# Input_channel.net
KiCad netlist of a schematic drawn in Altium Designer
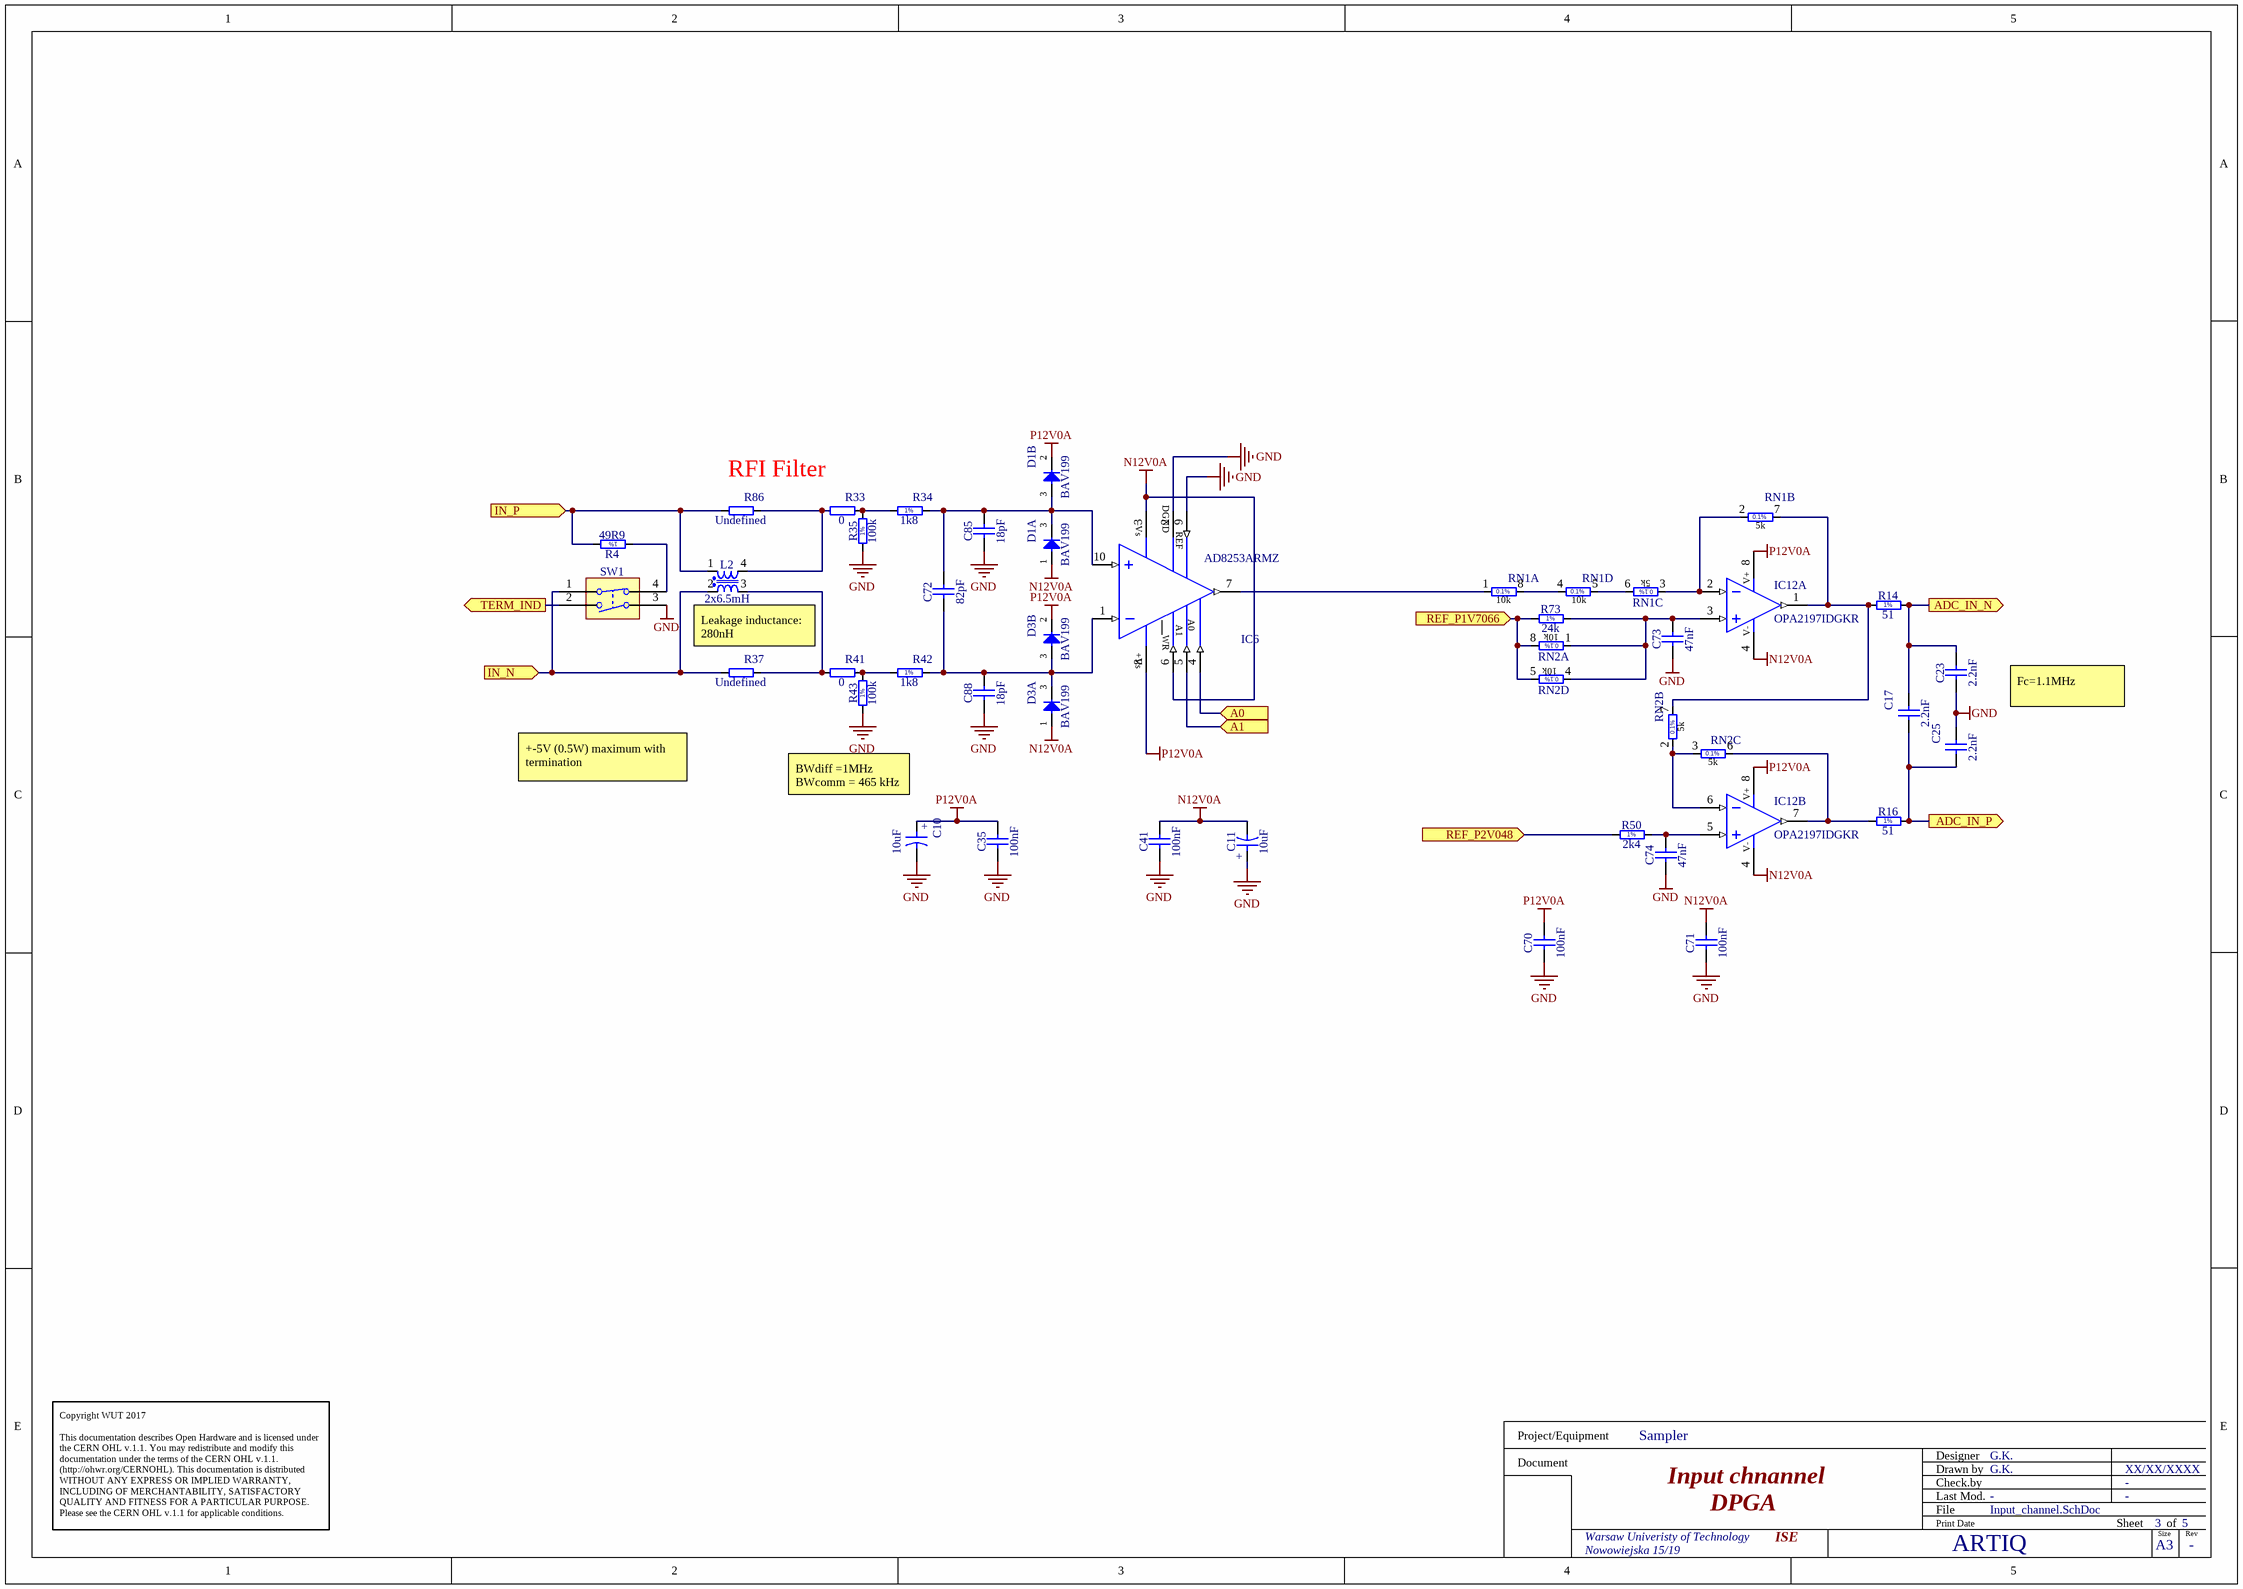
[diagram p0: Input_channel.SchDoc]

(export (version "E")
  (design (tool "Eeschema 10.0.6"))
  (components
    (comp (ref "C10")
      (value "10uF")
      (footprint "CAPMP3216X180N")
      (description "Polarised capacitor")
      (fields
        (field (name "PART NUMBER") "CTE3216-18_10UF_16V_20%_AVX_TCJ")
        (field (name "VOLTAGE") "16V")
        (field (name "AUTHOR") "CERN DEM JLC")
      )
      (libsource (lib "Capacitors") (part "Capacitor - polarized"))
    )
    (comp (ref "C11")
      (value "10uF")
      (footprint "CAPMP3216X180N")
      (description "Polarised capacitor")
      (fields
        (field (name "PART NUMBER") "CTE3216-18_10UF_16V_20%_AVX_TCJ")
        (field (name "VOLTAGE") "16V")
        (field (name "AUTHOR") "CERN DEM JLC")
      )
      (libsource (lib "Capacitors") (part "Capacitor - polarized"))
    )
    (comp (ref "C17")
      (value "2.2nF")
      (footprint "CAPC2013X100N")
      (description "Non-polarised capacitor")
      (fields
        (field (name "PART NUMBER") "CC0805_2.2NF_25V_1%_C0G")
        (field (name "VOLTAGE") "25V")
        (field (name "AUTHOR") "CERN DEM JLC")
      )
      (libsource (lib "Capacitors") (part "Capacitor - non polarized"))
    )
    (comp (ref "C23")
      (value "2.2nF")
      (footprint "CAPC2013X100N")
      (description "Non-polarised capacitor")
      (fields
        (field (name "PART NUMBER") "CC0805_2.2NF_25V_1%_C0G")
        (field (name "VOLTAGE") "25V")
        (field (name "AUTHOR") "CERN DEM JLC")
      )
      (libsource (lib "Capacitors") (part "Capacitor - non polarized"))
    )
    (comp (ref "C25")
      (value "2.2nF")
      (footprint "CAPC2013X100N")
      (description "Non-polarised capacitor")
      (fields
        (field (name "PART NUMBER") "CC0805_2.2NF_25V_1%_C0G")
        (field (name "VOLTAGE") "25V")
        (field (name "AUTHOR") "CERN DEM JLC")
      )
      (libsource (lib "Capacitors") (part "Capacitor - non polarized"))
    )
    (comp (ref "C35")
      (value "100nF")
      (footprint "CAPC1005X55N")
      (description "Non-polarised capacitor")
      (fields
        (field (name "PART NUMBER") "CC0402_100NF_16V_10%_X7R")
        (field (name "VOLTAGE") "16V")
        (field (name "AUTHOR") "CERN DEM JLC")
      )
      (libsource (lib "Capacitors") (part "Capacitor - non polarized"))
    )
    (comp (ref "C41")
      (value "100nF")
      (footprint "CAPC1005X55N")
      (description "Non-polarised capacitor")
      (fields
        (field (name "PART NUMBER") "CC0402_100NF_16V_10%_X7R")
        (field (name "VOLTAGE") "16V")
        (field (name "AUTHOR") "CERN DEM JLC")
      )
      (libsource (lib "Capacitors") (part "Capacitor - non polarized"))
    )
    (comp (ref "C70")
      (value "100nF")
      (footprint "CAPC1005X55N")
      (description "Non-polarised capacitor")
      (fields
        (field (name "PART NUMBER") "CC0402_100NF_16V_10%_X7R")
        (field (name "VOLTAGE") "16V")
        (field (name "AUTHOR") "CERN DEM JLC")
      )
      (libsource (lib "Capacitors") (part "Capacitor - non polarized"))
    )
    (comp (ref "C71")
      (value "100nF")
      (footprint "CAPC1005X55N")
      (description "Non-polarised capacitor")
      (fields
        (field (name "PART NUMBER") "CC0402_100NF_16V_10%_X7R")
        (field (name "VOLTAGE") "16V")
        (field (name "AUTHOR") "CERN DEM JLC")
      )
      (libsource (lib "Capacitors") (part "Capacitor - non polarized"))
    )
    (comp (ref "C72")
      (value "82pF")
      (footprint "CAPC2012X90N")
      (description "Non-polarised capacitor")
      (fields
        (field (name "PART NUMBER") "CC0805_82PF_100V_1%_NP0_AVX_08051A820FAT2A")
        (field (name "VOLTAGE") "100V")
        (field (name "AUTHOR") "CERN DEM WB")
      )
      (libsource (lib "Capacitors") (part "Capacitor - non polarized"))
    )
    (comp (ref "C73")
      (value "47nF")
      (footprint "CAPC2012X135N")
      (description "Non-polarised capacitor")
      (fields
        (field (name "PART NUMBER") "CC0805_47NF_25V_5%_C0G")
        (field (name "VOLTAGE") "25V")
        (field (name "AUTHOR") "CERN DEM JLC")
      )
      (libsource (lib "Capacitors") (part "Capacitor - non polarized"))
    )
    (comp (ref "C74")
      (value "47nF")
      (footprint "CAPC2012X135N")
      (description "Non-polarised capacitor")
      (fields
        (field (name "PART NUMBER") "CC0805_47NF_25V_5%_C0G")
        (field (name "VOLTAGE") "25V")
        (field (name "AUTHOR") "CERN DEM JLC")
      )
      (libsource (lib "Capacitors") (part "Capacitor - non polarized"))
    )
    (comp (ref "C85")
      (value "18pF")
      (footprint "CAPC1608X87N")
      (description "Non-polarised capacitor")
      (fields
        (field (name "PART NUMBER") "CC0603_18PF_50V_5%_NP0")
        (field (name "VOLTAGE") "50V")
        (field (name "AUTHOR") "CERN DEM JLC")
      )
      (libsource (lib "Capacitors") (part "Capacitor - non polarized"))
    )
    (comp (ref "C88")
      (value "18pF")
      (footprint "CAPC1608X87N")
      (description "Non-polarised capacitor")
      (fields
        (field (name "PART NUMBER") "CC0603_18PF_50V_5%_NP0")
        (field (name "VOLTAGE") "50V")
        (field (name "AUTHOR") "CERN DEM JLC")
      )
      (libsource (lib "Capacitors") (part "Capacitor - non polarized"))
    )
    (comp (ref "D1")
      (value "BAV199")
      (footprint "SOT95P240X110-3N")
      (description "Serial Diode")
      (fields
        (field (name "VOLTAGE") "75V")
        (field (name "POWER") "250mW")
        (field (name "AUTHOR") "CERN DEM JMW")
      )
      (libsource (lib "ICs And Semiconductors") (part "Diode x2 A1C3_A3C2"))
    )
    (comp (ref "D3")
      (value "BAV199")
      (footprint "SOT95P240X110-3N")
      (description "Serial Diode")
      (fields
        (field (name "VOLTAGE") "75V")
        (field (name "POWER") "250mW")
        (field (name "AUTHOR") "CERN DEM JMW")
      )
      (libsource (lib "ICs And Semiconductors") (part "Diode x2 A1C3_A3C2"))
    )
    (comp (ref "IC6")
      (value "AD8253ARMZ")
      (footprint "SOP50P490X110-10N")
      (description "10MHz, 20V/us, G= 1, 10, 100, 1000 iCMOS Programmable Gain Instrumentation Amplifier")
      (fields (field (name "MANUFACTURER") "ANALOG DEVICES") (field (name "AUTHOR") "CERN DEM JLC"))
      (libsource (lib "ICs And Semiconductors") (part "AD8253"))
    )
    (comp (ref "IC12")
      (value "OPA2197IDGKR")
      (footprint "SOP65P490X110-8N")
      (description "36-V, Precision, Rail-to-Rail Input Output, Low Offset Voltage Op Amp 8-VSSOP")
      (fields (field (name "MANUFACTURER") "TEXAS INSTRUMENTS") (field (name "AUTHOR") "GK"))
      (libsource (lib "LIBRARY_SCH") (part "OA_OPA2197IDGKR"))
    )
    (comp (ref "L2")
      (value "2x6.5mH")
      (footprint "IND_WURTH_WE-SL2")
      (description "Inductor Common Mode")
      (fields
        (field (name "PART NUMBER") "IND_6.5MH_50%_WURTH_WE-SL2-744229")
        (field (name "POWER") "400mA")
        (field (name "AUTHOR") "CERN DEM JLC")
      )
      (libsource (lib "Inductors & Transformers") (part "Inductor Common Mode 1Dot-4 2Dot-3"))
    )
    (comp (ref "R4")
      (value "49R9")
      (footprint "RESC6331X70N")
      (description "Resistor - 1%")
      (fields
        (field (name "PART NUMBER") "R2512_49R9_1%_1W_100PPM_VISHAY_CRCW")
        (field (name "POWER") "1W")
        (field (name "AUTHOR") "CERN DEM JLC")
      )
      (libsource (lib "Resistors") (part "Resistor - 1%"))
    )
    (comp (ref "R14")
      (value "51")
      (footprint "RESC1005X40N")
      (description "Resistor - 1%")
      (fields
        (field (name "PART NUMBER") "R0402_51R_1%_0.0625W_100PPM")
        (field (name "POWER") "0.0625W")
        (field (name "AUTHOR") "CERN DEM JLC")
      )
      (libsource (lib "Resistors") (part "Resistor - 1%"))
    )
    (comp (ref "R16")
      (value "51")
      (footprint "RESC1005X40N")
      (description "Resistor - 1%")
      (fields
        (field (name "PART NUMBER") "R0402_51R_1%_0.0625W_100PPM")
        (field (name "POWER") "0.0625W")
        (field (name "AUTHOR") "CERN DEM JLC")
      )
      (libsource (lib "Resistors") (part "Resistor - 1%"))
    )
    (comp (ref "R33")
      (value "0")
      (footprint "RESC1608X55N")
      (description "Resistor")
      (fields
        (field (name "PART NUMBER") "R0603_0R_JUMPER")
        (field (name "MANUFACTURER") "GENERIC")
        (field (name "AUTHOR") "CERN DEM JLC")
      )
      (libsource (lib "Resistors") (part "Resistor"))
    )
    (comp (ref "R34")
      (value "1k8")
      (footprint "RESC1608X55N")
      (description "Resistor - 1%")
      (fields
        (field (name "PART NUMBER") "R0603_1K8_1%_0.1W_100PPM")
        (field (name "POWER") "0.1W")
        (field (name "AUTHOR") "CERN DEM JLC")
      )
      (libsource (lib "Resistors") (part "Resistor - 1%"))
    )
    (comp (ref "R35")
      (value "100k")
      (footprint "RESC1608X55N")
      (description "Resistor - 1%")
      (fields
        (field (name "PART NUMBER") "R0603_100K_1%_0.1W_100PPM")
        (field (name "POWER") "0.1W")
        (field (name "AUTHOR") "CERN DEM JLC")
      )
      (libsource (lib "Resistors") (part "Resistor - 1%"))
    )
    (comp (ref "R37")
      (value "Undefined")
      (footprint "RESC1608X55N")
      (description "Resistor")
      (fields (field (name "PART NUMBER") "R0603_NO-VALUE") (field (name "AUTHOR") "CERN DEM JLC"))
      (libsource (lib "Resistors") (part "Resistor"))
    )
    (comp (ref "R41")
      (value "0")
      (footprint "RESC1608X55N")
      (description "Resistor")
      (fields
        (field (name "PART NUMBER") "R0603_0R_JUMPER")
        (field (name "MANUFACTURER") "GENERIC")
        (field (name "AUTHOR") "CERN DEM JLC")
      )
      (libsource (lib "Resistors") (part "Resistor"))
    )
    (comp (ref "R42")
      (value "1k8")
      (footprint "RESC1608X55N")
      (description "Resistor - 1%")
      (fields
        (field (name "PART NUMBER") "R0603_1K8_1%_0.1W_100PPM")
        (field (name "POWER") "0.1W")
        (field (name "AUTHOR") "CERN DEM JLC")
      )
      (libsource (lib "Resistors") (part "Resistor - 1%"))
    )
    (comp (ref "R43")
      (value "100k")
      (footprint "RESC1608X55N")
      (description "Resistor - 1%")
      (fields
        (field (name "PART NUMBER") "R0603_100K_1%_0.1W_100PPM")
        (field (name "POWER") "0.1W")
        (field (name "AUTHOR") "CERN DEM JLC")
      )
      (libsource (lib "Resistors") (part "Resistor - 1%"))
    )
    (comp (ref "R50")
      (value "2k4")
      (footprint "RESC1005X40N")
      (description "Resistor - 1%")
      (fields
        (field (name "PART NUMBER") "R0402_2K4_1%_0.0625W_100PPM")
        (field (name "POWER") "0.0625W")
        (field (name "AUTHOR") "CERN DEM JLC")
      )
      (libsource (lib "Resistors") (part "Resistor - 1%"))
    )
    (comp (ref "R73")
      (value "24k")
      (footprint "RESC1608X55N")
      (description "Resistor - 1%")
      (fields
        (field (name "PART NUMBER") "R0603_24K_1%_0.1W_100PPM")
        (field (name "POWER") "0.1W")
        (field (name "AUTHOR") "CERN DEM JLC")
      )
      (libsource (lib "Resistors") (part "Resistor - 1%"))
    )
    (comp (ref "R86")
      (value "Undefined")
      (footprint "RESC1608X55N")
      (description "Resistor")
      (fields (field (name "PART NUMBER") "R0603_NO-VALUE") (field (name "AUTHOR") "CERN DEM JLC"))
      (libsource (lib "Resistors") (part "Resistor"))
    )
    (comp (ref "RN1")
      (value "10k 5K 5K 10K")
      (footprint "SOIC127P600X175-8N")
      (description "DIL8 Resistor Network 4 Resistors 10k-5k-5k-10k 0.1%")
      (fields
        (field (name "PART NUMBER") "RN_10K_5K_VISHAY_AORN2-1AT3")
        (field (name "POWER") "4x0.1W")
        (field (name "AUTHOR") "CERN DEM JLC")
      )
      (libsource (lib "Resistors") (part "RN DIL8_4xR_10k-5k-5k-10k_0.1%"))
    )
    (comp (ref "RN2")
      (value "10k 5K 5K 10K")
      (footprint "SOIC127P600X175-8N")
      (description "DIL8 Resistor Network 4 Resistors 10k-5k-5k-10k 0.1%")
      (fields
        (field (name "PART NUMBER") "RN_10K_5K_VISHAY_AORN2-1AT3")
        (field (name "POWER") "4x0.1W")
        (field (name "AUTHOR") "CERN DEM JLC")
      )
      (libsource (lib "Resistors") (part "RN DIL8_4xR_10k-5k-5k-10k_0.1%"))
    )
    (comp (ref "SW1")
      (value "Switch")
      (footprint "SW_CTS_204-121ST")
      (description "2x SPST DIP Switch 1NO + 1NF")
      (fields
        (field (name "PART NUMBER") "SW_CTS_204-121ST")
        (field (name "MANUFACTURER") "CTS")
        (field (name "AUTHOR") "CERN DEM JLC")
      )
      (libsource (lib "Eletro-mechanical") (part "SW_CTS_204-121ST"))
    )
  )
  (nets
    (net (code "1") (name "/A0") (class "Default")
      (node (ref "IC6") (pin "4") (pinfunction "A0_4") (pintype "input"))
    )
    (net (code "2") (name "/A1") (class "Default")
      (node (ref "IC6") (pin "5") (pinfunction "A1_5") (pintype "input"))
    )
    (net (code "3") (name "/ADC_IN_N") (class "Default")
      (node (ref "C17") (pin "2") (pinfunction "2_2") (pintype "passive"))
      (node (ref "C23") (pin "2") (pinfunction "2_2") (pintype "passive"))
      (node (ref "R14") (pin "2") (pinfunction "2_2") (pintype "passive"))
    )
    (net (code "4") (name "/ADC_IN_P") (class "Default")
      (node (ref "C17") (pin "1") (pinfunction "1_1") (pintype "passive"))
      (node (ref "C25") (pin "1") (pinfunction "1_1") (pintype "passive"))
      (node (ref "R16") (pin "2") (pinfunction "2_2") (pintype "passive"))
    )
    (net (code "5") (name "/IN_N") (class "Default")
      (node (ref "L2") (pin "2") (pinfunction "2_2") (pintype "passive"))
      (node (ref "R37") (pin "1") (pinfunction "1_1") (pintype "passive"))
      (node (ref "SW1") (pin "1") (pinfunction "1_1") (pintype "passive"))
    )
    (net (code "6") (name "/IN_P") (class "Default")
      (node (ref "L2") (pin "1") (pinfunction "1_1") (pintype "passive"))
      (node (ref "R4") (pin "2") (pinfunction "2_2") (pintype "passive"))
      (node (ref "R86") (pin "1") (pinfunction "1_1") (pintype "passive"))
    )
    (net (code "7") (name "/REF_P1V7066") (class "Default")
      (node (ref "R73") (pin "1") (pinfunction "1_1") (pintype "passive"))
      (node (ref "RN2") (pin "5") (pinfunction "5_5") (pintype "passive"))
      (node (ref "RN2") (pin "8") (pinfunction "8_8") (pintype "passive"))
    )
    (net (code "8") (name "/REF_P2V048") (class "Default")
      (node (ref "R50") (pin "1") (pinfunction "1_1") (pintype "passive"))
    )
    (net (code "9") (name "/TERM_IND") (class "Default")
      (node (ref "SW1") (pin "2") (pinfunction "2_2") (pintype "passive"))
    )
    (net (code "10") (name "GND") (class "Default")
      (node (ref "C10") (pin "2") (pinfunction "2_2") (pintype "passive"))
      (node (ref "C11") (pin "1") (pinfunction "1_1") (pintype "passive"))
      (node (ref "C23") (pin "1") (pinfunction "1_1") (pintype "passive"))
      (node (ref "C25") (pin "2") (pinfunction "2_2") (pintype "passive"))
      (node (ref "C35") (pin "1") (pinfunction "1_1") (pintype "passive"))
      (node (ref "C41") (pin "1") (pinfunction "1_1") (pintype "passive"))
      (node (ref "C70") (pin "1") (pinfunction "1_1") (pintype "passive"))
      (node (ref "C71") (pin "1") (pinfunction "1_1") (pintype "passive"))
      (node (ref "C73") (pin "1") (pinfunction "1_1") (pintype "passive"))
      (node (ref "C74") (pin "1") (pinfunction "1_1") (pintype "passive"))
      (node (ref "C85") (pin "1") (pinfunction "1_1") (pintype "passive"))
      (node (ref "C88") (pin "1") (pinfunction "1_1") (pintype "passive"))
      (node (ref "IC6") (pin "2") (pinfunction "DGND_2") (pintype "power_in"))
      (node (ref "IC6") (pin "9") (pinfunction "REF_9") (pintype "input"))
      (node (ref "R35") (pin "1") (pinfunction "1_1") (pintype "passive"))
      (node (ref "R43") (pin "1") (pinfunction "1_1") (pintype "passive"))
      (node (ref "SW1") (pin "3") (pinfunction "3_3") (pintype "passive"))
    )
    (net (code "11") (name "N12V0A") (class "Default")
      (node (ref "C11") (pin "2") (pinfunction "2_2") (pintype "passive"))
      (node (ref "C41") (pin "2") (pinfunction "2_2") (pintype "passive"))
      (node (ref "C71") (pin "2") (pinfunction "2_2") (pintype "passive"))
      (node (ref "D1") (pin "1") (pinfunction "A_1") (pintype "passive"))
      (node (ref "D3") (pin "1") (pinfunction "A_1") (pintype "passive"))
      (node (ref "IC12") (pin "4") (pinfunction "V-_4") (pintype "power_in"))
      (node (ref "IC6") (pin "3") (pinfunction "-VS_3") (pintype "power_in"))
      (node (ref "IC6") (pin "6") (pinfunction "~{WR}_6") (pintype "input"))
    )
    (net (code "12") (name "Net-(D1A-COMAC)") (class "Default")
      (node (ref "C72") (pin "2") (pinfunction "2_2") (pintype "passive"))
      (node (ref "C85") (pin "2") (pinfunction "2_2") (pintype "passive"))
      (node (ref "D1") (pin "3") (pinfunction "COMAC_3") (pintype "passive"))
      (node (ref "IC6") (pin "10") (pinfunction "+IN_10") (pintype "input"))
      (node (ref "R34") (pin "2") (pinfunction "2_2") (pintype "passive"))
    )
    (net (code "13") (name "Net-(D3A-COMAC)") (class "Default")
      (node (ref "C72") (pin "1") (pinfunction "1_1") (pintype "passive"))
      (node (ref "C88") (pin "2") (pinfunction "2_2") (pintype "passive"))
      (node (ref "D3") (pin "3") (pinfunction "COMAC_3") (pintype "passive"))
      (node (ref "IC6") (pin "1") (pinfunction "-IN_1") (pintype "input"))
      (node (ref "R42") (pin "2") (pinfunction "2_2") (pintype "passive"))
    )
    (net (code "14") (name "Net-(IC6-OUT)") (class "Default")
      (node (ref "IC6") (pin "7") (pinfunction "OUT_7") (pintype "output"))
      (node (ref "RN1") (pin "1") (pinfunction "1_1") (pintype "passive"))
    )
    (net (code "15") (name "Net-(IC12A-IN+)") (class "Default")
      (node (ref "C73") (pin "2") (pinfunction "2_2") (pintype "passive"))
      (node (ref "IC12") (pin "3") (pinfunction "IN+_3") (pintype "input"))
      (node (ref "R73") (pin "2") (pinfunction "2_2") (pintype "passive"))
      (node (ref "RN2") (pin "1") (pinfunction "1_1") (pintype "passive"))
      (node (ref "RN2") (pin "4") (pinfunction "4_4") (pintype "passive"))
    )
    (net (code "16") (name "Net-(IC12A-IN-)") (class "Default")
      (node (ref "IC12") (pin "2") (pinfunction "IN-_2") (pintype "input"))
      (node (ref "RN1") (pin "2") (pinfunction "2_2") (pintype "passive"))
      (node (ref "RN1") (pin "3") (pinfunction "3_3") (pintype "passive"))
    )
    (net (code "17") (name "Net-(IC12A-OUT)") (class "Default")
      (node (ref "IC12") (pin "1") (pinfunction "OUT_1") (pintype "output"))
      (node (ref "R14") (pin "1") (pinfunction "1_1") (pintype "passive"))
      (node (ref "RN1") (pin "7") (pinfunction "7_7") (pintype "passive"))
      (node (ref "RN2") (pin "7") (pinfunction "7_7") (pintype "passive"))
    )
    (net (code "18") (name "Net-(IC12B-IN+)") (class "Default")
      (node (ref "C74") (pin "2") (pinfunction "2_2") (pintype "passive"))
      (node (ref "IC12") (pin "5") (pinfunction "IN+_5") (pintype "input"))
      (node (ref "R50") (pin "2") (pinfunction "2_2") (pintype "passive"))
    )
    (net (code "19") (name "Net-(IC12B-IN-)") (class "Default")
      (node (ref "IC12") (pin "6") (pinfunction "IN-_6") (pintype "input"))
      (node (ref "RN2") (pin "2") (pinfunction "2_2") (pintype "passive"))
      (node (ref "RN2") (pin "3") (pinfunction "3_3") (pintype "passive"))
    )
    (net (code "20") (name "Net-(IC12B-OUT)") (class "Default")
      (node (ref "IC12") (pin "7") (pinfunction "OUT_7") (pintype "output"))
      (node (ref "R16") (pin "1") (pinfunction "1_1") (pintype "passive"))
      (node (ref "RN2") (pin "6") (pinfunction "6_6") (pintype "passive"))
    )
    (net (code "21") (name "Net-(L2-Pad3)") (class "Default")
      (node (ref "L2") (pin "3") (pinfunction "3_3") (pintype "passive"))
      (node (ref "R37") (pin "2") (pinfunction "2_2") (pintype "passive"))
      (node (ref "R41") (pin "1") (pinfunction "1_1") (pintype "passive"))
    )
    (net (code "22") (name "Net-(L2-Pad4)") (class "Default")
      (node (ref "L2") (pin "4") (pinfunction "4_4") (pintype "passive"))
      (node (ref "R33") (pin "1") (pinfunction "1_1") (pintype "passive"))
      (node (ref "R86") (pin "2") (pinfunction "2_2") (pintype "passive"))
    )
    (net (code "23") (name "Net-(R4-Pad1)") (class "Default")
      (node (ref "R4") (pin "1") (pinfunction "1_1") (pintype "passive"))
      (node (ref "SW1") (pin "4") (pinfunction "4_4") (pintype "passive"))
    )
    (net (code "24") (name "Net-(R33-Pad2)") (class "Default")
      (node (ref "R33") (pin "2") (pinfunction "2_2") (pintype "passive"))
      (node (ref "R34") (pin "1") (pinfunction "1_1") (pintype "passive"))
      (node (ref "R35") (pin "2") (pinfunction "2_2") (pintype "passive"))
    )
    (net (code "25") (name "Net-(R41-Pad2)") (class "Default")
      (node (ref "R41") (pin "2") (pinfunction "2_2") (pintype "passive"))
      (node (ref "R42") (pin "1") (pinfunction "1_1") (pintype "passive"))
      (node (ref "R43") (pin "2") (pinfunction "2_2") (pintype "passive"))
    )
    (net (code "26") (name "Net-(RN1-Pad4)") (class "Default")
      (node (ref "RN1") (pin "4") (pinfunction "4_4") (pintype "passive"))
      (node (ref "RN1") (pin "8") (pinfunction "8_8") (pintype "passive"))
    )
    (net (code "27") (name "Net-(RN1-Pad5)") (class "Default")
      (node (ref "RN1") (pin "5") (pinfunction "5_5") (pintype "passive"))
      (node (ref "RN1") (pin "6") (pinfunction "6_6") (pintype "passive"))
    )
    (net (code "28") (name "P12V0A") (class "Default")
      (node (ref "C10") (pin "1") (pinfunction "1_1") (pintype "passive"))
      (node (ref "C35") (pin "2") (pinfunction "2_2") (pintype "passive"))
      (node (ref "C70") (pin "2") (pinfunction "2_2") (pintype "passive"))
      (node (ref "D1") (pin "2") (pinfunction "C_2") (pintype "passive"))
      (node (ref "D3") (pin "2") (pinfunction "C_2") (pintype "passive"))
      (node (ref "IC12") (pin "8") (pinfunction "V+_8") (pintype "power_in"))
      (node (ref "IC6") (pin "8") (pinfunction "+VS_8") (pintype "power_in"))
    )
  )
)
